# McPiFace-Status-V2.net
KiCad netlist of a schematic drawn in EAGLE
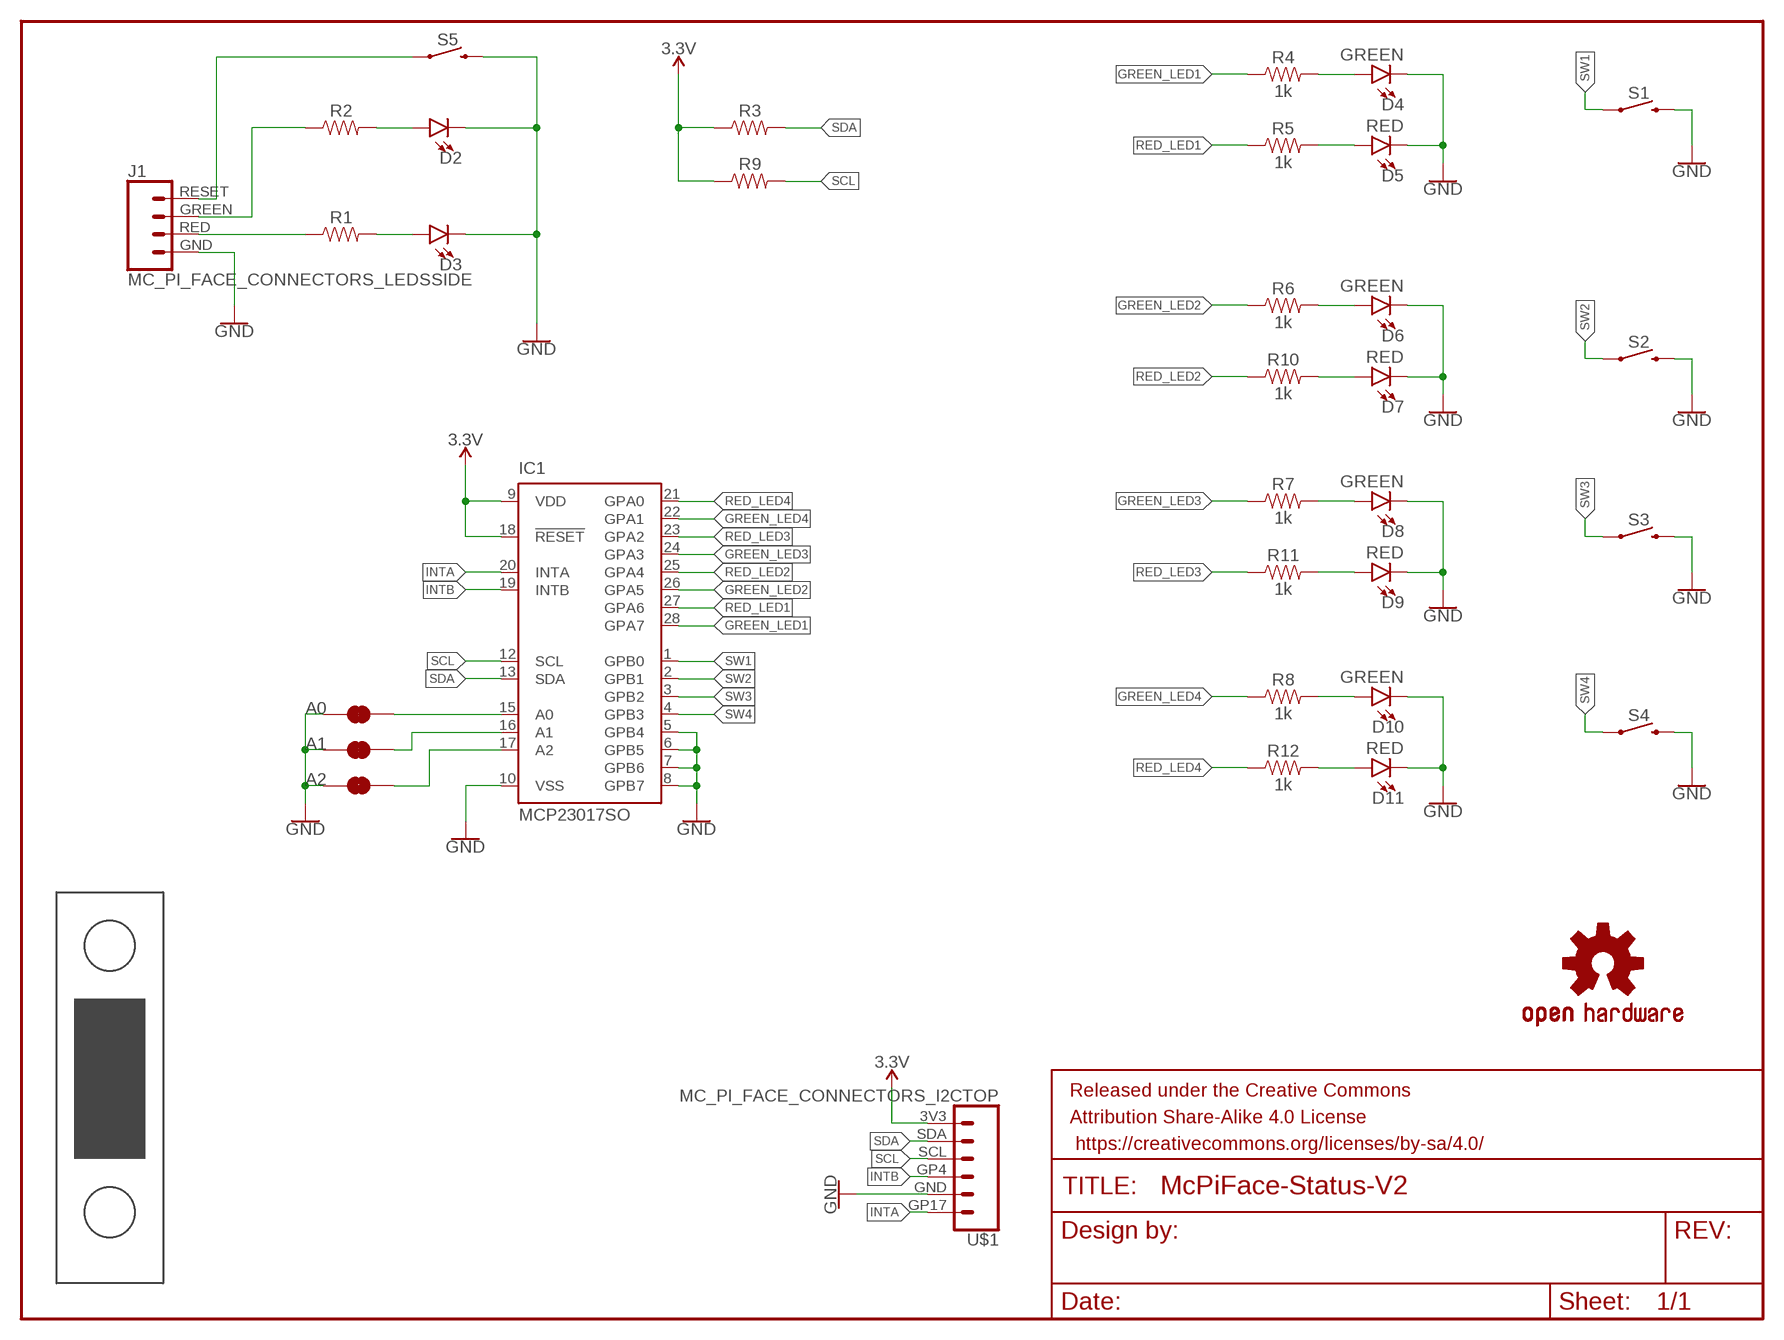
[diagram p0: schematic, sheet 1]

(export (version "E")
  (design (tool "Eeschema 10.0.6"))
  (components
    (comp (ref "A0")
      (value "JUMPER-SMT_2_NC_TRACE_SILK")
      (footprint "eagle-import:SMT-JUMPER_2_NC_TRACE_SILK")
      (libsource (lib "eagle-import") (part "JUMPER-SMT_2_NC_TRACE_SILK"))
    )
    (comp (ref "A1")
      (value "JUMPER-SMT_2_NC_TRACE_SILK")
      (footprint "eagle-import:SMT-JUMPER_2_NC_TRACE_SILK")
      (libsource (lib "eagle-import") (part "JUMPER-SMT_2_NC_TRACE_SILK"))
    )
    (comp (ref "A2")
      (value "JUMPER-SMT_2_NC_TRACE_SILK")
      (footprint "eagle-import:SMT-JUMPER_2_NC_TRACE_SILK")
      (libsource (lib "eagle-import") (part "JUMPER-SMT_2_NC_TRACE_SILK"))
    )
    (comp (ref "D2")
      (value "LEDLED-1206-BOTTOM-2.0MM-GREEN")
      (footprint "eagle-import:LED-1206-BOTTOM-2.0MM")
      (libsource (lib "eagle-import") (part "LEDLED-1206-BOTTOM-2.0MM-GREEN"))
    )
    (comp (ref "D3")
      (value "LEDLED-1206-BOTTOM-2.0MM-RED")
      (footprint "eagle-import:LED-1206-BOTTOM-2.0MM")
      (libsource (lib "eagle-import") (part "LEDLED-1206-BOTTOM-2.0MM-RED"))
    )
    (comp (ref "D4")
      (value "GREEN")
      (footprint "eagle-import:LED-1206-BOTTOM-2.0MM")
      (libsource (lib "eagle-import") (part "LEDLED-1206-BOTTOM-2.0MM-GREEN"))
    )
    (comp (ref "D5")
      (value "RED")
      (footprint "eagle-import:LED-1206-BOTTOM-2.0MM")
      (libsource (lib "eagle-import") (part "LEDLED-1206-BOTTOM-2.0MM-RED"))
    )
    (comp (ref "D6")
      (value "GREEN")
      (footprint "eagle-import:LED-1206-BOTTOM-2.0MM")
      (libsource (lib "eagle-import") (part "LEDLED-1206-BOTTOM-2.0MM-GREEN"))
    )
    (comp (ref "D7")
      (value "RED")
      (footprint "eagle-import:LED-1206-BOTTOM-2.0MM")
      (libsource (lib "eagle-import") (part "LEDLED-1206-BOTTOM-2.0MM-RED"))
    )
    (comp (ref "D8")
      (value "GREEN")
      (footprint "eagle-import:LED-1206-BOTTOM-2.0MM")
      (libsource (lib "eagle-import") (part "LEDLED-1206-BOTTOM-2.0MM-GREEN"))
    )
    (comp (ref "D9")
      (value "RED")
      (footprint "eagle-import:LED-1206-BOTTOM-2.0MM")
      (libsource (lib "eagle-import") (part "LEDLED-1206-BOTTOM-2.0MM-RED"))
    )
    (comp (ref "D10")
      (value "GREEN")
      (footprint "eagle-import:LED-1206-BOTTOM-2.0MM")
      (libsource (lib "eagle-import") (part "LEDLED-1206-BOTTOM-2.0MM-GREEN"))
    )
    (comp (ref "D11")
      (value "RED")
      (footprint "eagle-import:LED-1206-BOTTOM-2.0MM")
      (libsource (lib "eagle-import") (part "LEDLED-1206-BOTTOM-2.0MM-RED"))
    )
    (comp (ref "FP1")
      (value "MC_PI_FACE_PANELDOUBLE")
      (footprint "eagle-import:MC_PI_DOUBLE_FACE")
      (libsource (lib "eagle-import") (part "MC_PI_FACE_PANELDOUBLE"))
    )
    (comp (ref "FRAME1")
      (value "FRAME-LETTER")
      (footprint "eagle-import:CREATIVE_COMMONS")
      (libsource (lib "eagle-import") (part "FRAME-LETTER"))
    )
    (comp (ref "IC1")
      (value "MCP23017SO")
      (footprint "eagle-import:SO28W")
      (libsource (lib "eagle-import") (part "MCP23017SO"))
    )
    (comp (ref "J1")
      (value "MC_PI_FACE_CONNECTORS_LEDSSIDE")
      (footprint "eagle-import:JST-4-SH-1.0MM-SIDE")
      (fields (field (name "MFG") "SM04B-SRSS-TB(LF)(SN)"))
      (libsource (lib "eagle-import") (part "MC_PI_FACE_CONNECTORS_LEDSSIDE"))
    )
    (comp (ref "LOGO1")
      (value "OSHW-LOGOL")
      (footprint "eagle-import:OSHW-LOGO-L")
      (libsource (lib "eagle-import") (part "OSHW-LOGOL"))
    )
    (comp (ref "R1")
      (value "RESISTOR0805")
      (footprint "eagle-import:0805")
      (libsource (lib "eagle-import") (part "RESISTOR0805"))
    )
    (comp (ref "R2")
      (value "RESISTOR0805")
      (footprint "eagle-import:0805")
      (libsource (lib "eagle-import") (part "RESISTOR0805"))
    )
    (comp (ref "R3")
      (value "RESISTOR0805")
      (footprint "eagle-import:0805")
      (libsource (lib "eagle-import") (part "RESISTOR0805"))
    )
    (comp (ref "R4")
      (value "1k")
      (footprint "eagle-import:0805")
      (libsource (lib "eagle-import") (part "RESISTOR0805"))
    )
    (comp (ref "R5")
      (value "1k")
      (footprint "eagle-import:0805")
      (libsource (lib "eagle-import") (part "RESISTOR0805"))
    )
    (comp (ref "R6")
      (value "1k")
      (footprint "eagle-import:0805")
      (libsource (lib "eagle-import") (part "RESISTOR0805"))
    )
    (comp (ref "R7")
      (value "1k")
      (footprint "eagle-import:0805")
      (libsource (lib "eagle-import") (part "RESISTOR0805"))
    )
    (comp (ref "R8")
      (value "1k")
      (footprint "eagle-import:0805")
      (libsource (lib "eagle-import") (part "RESISTOR0805"))
    )
    (comp (ref "R9")
      (value "RESISTOR0805")
      (footprint "eagle-import:0805")
      (libsource (lib "eagle-import") (part "RESISTOR0805"))
    )
    (comp (ref "R10")
      (value "1k")
      (footprint "eagle-import:0805")
      (libsource (lib "eagle-import") (part "RESISTOR0805"))
    )
    (comp (ref "R11")
      (value "1k")
      (footprint "eagle-import:0805")
      (libsource (lib "eagle-import") (part "RESISTOR0805"))
    )
    (comp (ref "R12")
      (value "1k")
      (footprint "eagle-import:0805")
      (libsource (lib "eagle-import") (part "RESISTOR0805"))
    )
    (comp (ref "S1")
      (value "MOMENTARY-SWITCH-SPSTTACKTILE_SWITCH_PTH_6.0MM_NO_TOP_RESIST")
      (footprint "eagle-import:TACTILE_SWITCH_PTH_6.0MM_NO_TOP_RESIST")
      (libsource (lib "eagle-import") (part "MOMENTARY-SWITCH-SPSTTACKTILE_SWITCH_PTH_6.0MM_NO_TOP_RESIST"))
    )
    (comp (ref "S2")
      (value "MOMENTARY-SWITCH-SPSTTACKTILE_SWITCH_PTH_6.0MM_NO_TOP_RESIST")
      (footprint "eagle-import:TACTILE_SWITCH_PTH_6.0MM_NO_TOP_RESIST")
      (libsource (lib "eagle-import") (part "MOMENTARY-SWITCH-SPSTTACKTILE_SWITCH_PTH_6.0MM_NO_TOP_RESIST"))
    )
    (comp (ref "S3")
      (value "MOMENTARY-SWITCH-SPSTTACKTILE_SWITCH_PTH_6.0MM_NO_TOP_RESIST")
      (footprint "eagle-import:TACTILE_SWITCH_PTH_6.0MM_NO_TOP_RESIST")
      (libsource (lib "eagle-import") (part "MOMENTARY-SWITCH-SPSTTACKTILE_SWITCH_PTH_6.0MM_NO_TOP_RESIST"))
    )
    (comp (ref "S4")
      (value "MOMENTARY-SWITCH-SPSTTACKTILE_SWITCH_PTH_6.0MM_NO_TOP_RESIST")
      (footprint "eagle-import:TACTILE_SWITCH_PTH_6.0MM_NO_TOP_RESIST")
      (libsource (lib "eagle-import") (part "MOMENTARY-SWITCH-SPSTTACKTILE_SWITCH_PTH_6.0MM_NO_TOP_RESIST"))
    )
    (comp (ref "S5")
      (value "MOMENTARY-SWITCH-SPSTTACKTILE_SWITCH_PTH_6.0MM_NO_TOP_RESIST")
      (footprint "eagle-import:TACTILE_SWITCH_PTH_6.0MM_NO_TOP_RESIST")
      (libsource (lib "eagle-import") (part "MOMENTARY-SWITCH-SPSTTACKTILE_SWITCH_PTH_6.0MM_NO_TOP_RESIST"))
    )
    (comp (ref "U$1")
      (value "MC_PI_FACE_CONNECTORS_I2CTOP")
      (footprint "eagle-import:JST-6-SH-1.0MM-TOP")
      (libsource (lib "eagle-import") (part "MC_PI_FACE_CONNECTORS_I2CTOP"))
    )
  )
  (nets
    (net (code "1") (name "3.3V") (class "Default")
      (node (ref "IC1") (pin "18") (pinfunction "~{RESET}_18") (pintype "input"))
      (node (ref "IC1") (pin "9") (pinfunction "VDD_9") (pintype "power_in"))
      (node (ref "R3") (pin "1") (pinfunction "1_1") (pintype "passive"))
      (node (ref "R9") (pin "1") (pinfunction "1_1") (pintype "passive"))
      (node (ref "U$1") (pin "3V3") (pinfunction "3V3_3V3") (pintype "power_in"))
    )
    (net (code "2") (name "GND") (class "Default")
      (node (ref "A0") (pin "1") (pinfunction "1_1") (pintype "passive"))
      (node (ref "A1") (pin "1") (pinfunction "1_1") (pintype "passive"))
      (node (ref "A2") (pin "1") (pinfunction "1_1") (pintype "passive"))
      (node (ref "D10") (pin "C") (pinfunction "C_C") (pintype "passive"))
      (node (ref "D11") (pin "C") (pinfunction "C_C") (pintype "passive"))
      (node (ref "D2") (pin "C") (pinfunction "C_C") (pintype "passive"))
      (node (ref "D3") (pin "C") (pinfunction "C_C") (pintype "passive"))
      (node (ref "D4") (pin "C") (pinfunction "C_C") (pintype "passive"))
      (node (ref "D5") (pin "C") (pinfunction "C_C") (pintype "passive"))
      (node (ref "D6") (pin "C") (pinfunction "C_C") (pintype "passive"))
      (node (ref "D7") (pin "C") (pinfunction "C_C") (pintype "passive"))
      (node (ref "D8") (pin "C") (pinfunction "C_C") (pintype "passive"))
      (node (ref "D9") (pin "C") (pinfunction "C_C") (pintype "passive"))
      (node (ref "IC1") (pin "10") (pinfunction "VSS_10") (pintype "power_in"))
      (node (ref "IC1") (pin "5") (pinfunction "GPB4_5") (pintype "bidirectional"))
      (node (ref "IC1") (pin "6") (pinfunction "GPB5_6") (pintype "bidirectional"))
      (node (ref "IC1") (pin "7") (pinfunction "GPB6_7") (pintype "bidirectional"))
      (node (ref "IC1") (pin "8") (pinfunction "GPB7_8") (pintype "bidirectional"))
      (node (ref "J1") (pin "GND") (pinfunction "GND_GND") (pintype "power_in"))
      (node (ref "S1") (pin "3") (pinfunction "2_3") (pintype "passive"))
      (node (ref "S2") (pin "3") (pinfunction "2_3") (pintype "passive"))
      (node (ref "S3") (pin "3") (pinfunction "2_3") (pintype "passive"))
      (node (ref "S4") (pin "3") (pinfunction "2_3") (pintype "passive"))
      (node (ref "S5") (pin "3") (pinfunction "2_3") (pintype "passive"))
      (node (ref "U$1") (pin "GND") (pinfunction "GND_GND") (pintype "power_in"))
    )
    (net (code "3") (name "GREEN_LED1") (class "Default")
      (node (ref "IC1") (pin "28") (pinfunction "GPA7_28") (pintype "bidirectional"))
      (node (ref "R4") (pin "1") (pinfunction "1_1") (pintype "passive"))
    )
    (net (code "4") (name "GREEN_LED2") (class "Default")
      (node (ref "IC1") (pin "26") (pinfunction "GPA5_26") (pintype "bidirectional"))
      (node (ref "R6") (pin "1") (pinfunction "1_1") (pintype "passive"))
    )
    (net (code "5") (name "GREEN_LED3") (class "Default")
      (node (ref "IC1") (pin "24") (pinfunction "GPA3_24") (pintype "bidirectional"))
      (node (ref "R7") (pin "1") (pinfunction "1_1") (pintype "passive"))
    )
    (net (code "6") (name "GREEN_LED4") (class "Default")
      (node (ref "IC1") (pin "22") (pinfunction "GPA1_22") (pintype "bidirectional"))
      (node (ref "R8") (pin "1") (pinfunction "1_1") (pintype "passive"))
    )
    (net (code "7") (name "INTA") (class "Default")
      (node (ref "IC1") (pin "20") (pinfunction "INTA_20") (pintype "output"))
      (node (ref "U$1") (pin "GP17") (pinfunction "GP17_GP17") (pintype "bidirectional"))
    )
    (net (code "8") (name "INTB") (class "Default")
      (node (ref "IC1") (pin "19") (pinfunction "INTB_19") (pintype "output"))
      (node (ref "U$1") (pin "GP4") (pinfunction "GP4_GP4") (pintype "bidirectional"))
    )
    (net (code "9") (name "Net-(D2-PadA)") (class "Default")
      (node (ref "D2") (pin "A") (pinfunction "A_A") (pintype "passive"))
      (node (ref "R2") (pin "2") (pinfunction "2_2") (pintype "passive"))
    )
    (net (code "10") (name "Net-(D3-PadA)") (class "Default")
      (node (ref "D3") (pin "A") (pinfunction "A_A") (pintype "passive"))
      (node (ref "R1") (pin "2") (pinfunction "2_2") (pintype "passive"))
    )
    (net (code "11") (name "Net-(D4-PadA)") (class "Default")
      (node (ref "D4") (pin "A") (pinfunction "A_A") (pintype "passive"))
      (node (ref "R4") (pin "2") (pinfunction "2_2") (pintype "passive"))
    )
    (net (code "12") (name "Net-(D5-PadA)") (class "Default")
      (node (ref "D5") (pin "A") (pinfunction "A_A") (pintype "passive"))
      (node (ref "R5") (pin "2") (pinfunction "2_2") (pintype "passive"))
    )
    (net (code "13") (name "Net-(D6-PadA)") (class "Default")
      (node (ref "D6") (pin "A") (pinfunction "A_A") (pintype "passive"))
      (node (ref "R6") (pin "2") (pinfunction "2_2") (pintype "passive"))
    )
    (net (code "14") (name "Net-(D7-PadA)") (class "Default")
      (node (ref "D7") (pin "A") (pinfunction "A_A") (pintype "passive"))
      (node (ref "R10") (pin "2") (pinfunction "2_2") (pintype "passive"))
    )
    (net (code "15") (name "Net-(D8-PadA)") (class "Default")
      (node (ref "D8") (pin "A") (pinfunction "A_A") (pintype "passive"))
      (node (ref "R7") (pin "2") (pinfunction "2_2") (pintype "passive"))
    )
    (net (code "16") (name "Net-(D9-PadA)") (class "Default")
      (node (ref "D9") (pin "A") (pinfunction "A_A") (pintype "passive"))
      (node (ref "R11") (pin "2") (pinfunction "2_2") (pintype "passive"))
    )
    (net (code "17") (name "Net-(D10-PadA)") (class "Default")
      (node (ref "D10") (pin "A") (pinfunction "A_A") (pintype "passive"))
      (node (ref "R8") (pin "2") (pinfunction "2_2") (pintype "passive"))
    )
    (net (code "18") (name "Net-(D11-PadA)") (class "Default")
      (node (ref "D11") (pin "A") (pinfunction "A_A") (pintype "passive"))
      (node (ref "R12") (pin "2") (pinfunction "2_2") (pintype "passive"))
    )
    (net (code "19") (name "Net-(IC1-A0)") (class "Default")
      (node (ref "A0") (pin "2") (pinfunction "2_2") (pintype "passive"))
      (node (ref "IC1") (pin "15") (pinfunction "A0_15") (pintype "input"))
    )
    (net (code "20") (name "Net-(IC1-A1)") (class "Default")
      (node (ref "A1") (pin "2") (pinfunction "2_2") (pintype "passive"))
      (node (ref "IC1") (pin "16") (pinfunction "A1_16") (pintype "input"))
    )
    (net (code "21") (name "Net-(IC1-A2)") (class "Default")
      (node (ref "A2") (pin "2") (pinfunction "2_2") (pintype "passive"))
      (node (ref "IC1") (pin "17") (pinfunction "A2_17") (pintype "input"))
    )
    (net (code "22") (name "Net-(J1-PadGREEN)") (class "Default")
      (node (ref "J1") (pin "GREEN") (pinfunction "GREEN_GREEN") (pintype "passive"))
      (node (ref "R2") (pin "1") (pinfunction "1_1") (pintype "passive"))
    )
    (net (code "23") (name "Net-(J1-PadRED)") (class "Default")
      (node (ref "J1") (pin "RED") (pinfunction "RED_RED") (pintype "passive"))
      (node (ref "R1") (pin "1") (pinfunction "1_1") (pintype "passive"))
    )
    (net (code "24") (name "Net-(J1-PadRESET)") (class "Default")
      (node (ref "J1") (pin "RESET") (pinfunction "RESET_RESET") (pintype "passive"))
      (node (ref "S5") (pin "1") (pinfunction "1_1") (pintype "passive"))
    )
    (net (code "25") (name "RED_LED1") (class "Default")
      (node (ref "IC1") (pin "27") (pinfunction "GPA6_27") (pintype "bidirectional"))
      (node (ref "R5") (pin "1") (pinfunction "1_1") (pintype "passive"))
    )
    (net (code "26") (name "RED_LED2") (class "Default")
      (node (ref "IC1") (pin "25") (pinfunction "GPA4_25") (pintype "bidirectional"))
      (node (ref "R10") (pin "1") (pinfunction "1_1") (pintype "passive"))
    )
    (net (code "27") (name "RED_LED3") (class "Default")
      (node (ref "IC1") (pin "23") (pinfunction "GPA2_23") (pintype "bidirectional"))
      (node (ref "R11") (pin "1") (pinfunction "1_1") (pintype "passive"))
    )
    (net (code "28") (name "RED_LED4") (class "Default")
      (node (ref "IC1") (pin "21") (pinfunction "GPA0_21") (pintype "bidirectional"))
      (node (ref "R12") (pin "1") (pinfunction "1_1") (pintype "passive"))
    )
    (net (code "29") (name "SCL") (class "Default")
      (node (ref "IC1") (pin "12") (pinfunction "SCL_12") (pintype "input"))
      (node (ref "R9") (pin "2") (pinfunction "2_2") (pintype "passive"))
      (node (ref "U$1") (pin "SCL") (pinfunction "SCL_SCL") (pintype "bidirectional"))
    )
    (net (code "30") (name "SDA") (class "Default")
      (node (ref "IC1") (pin "13") (pinfunction "SDA_13") (pintype "bidirectional"))
      (node (ref "R3") (pin "2") (pinfunction "2_2") (pintype "passive"))
      (node (ref "U$1") (pin "SDA") (pinfunction "SDA_SDA") (pintype "bidirectional"))
    )
    (net (code "31") (name "SW1") (class "Default")
      (node (ref "IC1") (pin "1") (pinfunction "GPB0_1") (pintype "bidirectional"))
      (node (ref "S1") (pin "1") (pinfunction "1_1") (pintype "passive"))
    )
    (net (code "32") (name "SW2") (class "Default")
      (node (ref "IC1") (pin "2") (pinfunction "GPB1_2") (pintype "bidirectional"))
      (node (ref "S2") (pin "1") (pinfunction "1_1") (pintype "passive"))
    )
    (net (code "33") (name "SW3") (class "Default")
      (node (ref "IC1") (pin "3") (pinfunction "GPB2_3") (pintype "bidirectional"))
      (node (ref "S3") (pin "1") (pinfunction "1_1") (pintype "passive"))
    )
    (net (code "34") (name "SW4") (class "Default")
      (node (ref "IC1") (pin "4") (pinfunction "GPB3_4") (pintype "bidirectional"))
      (node (ref "S4") (pin "1") (pinfunction "1_1") (pintype "passive"))
    )
  )
)
